# MotorCell.net
KiCad netlist of a schematic drawn in Altium Designer
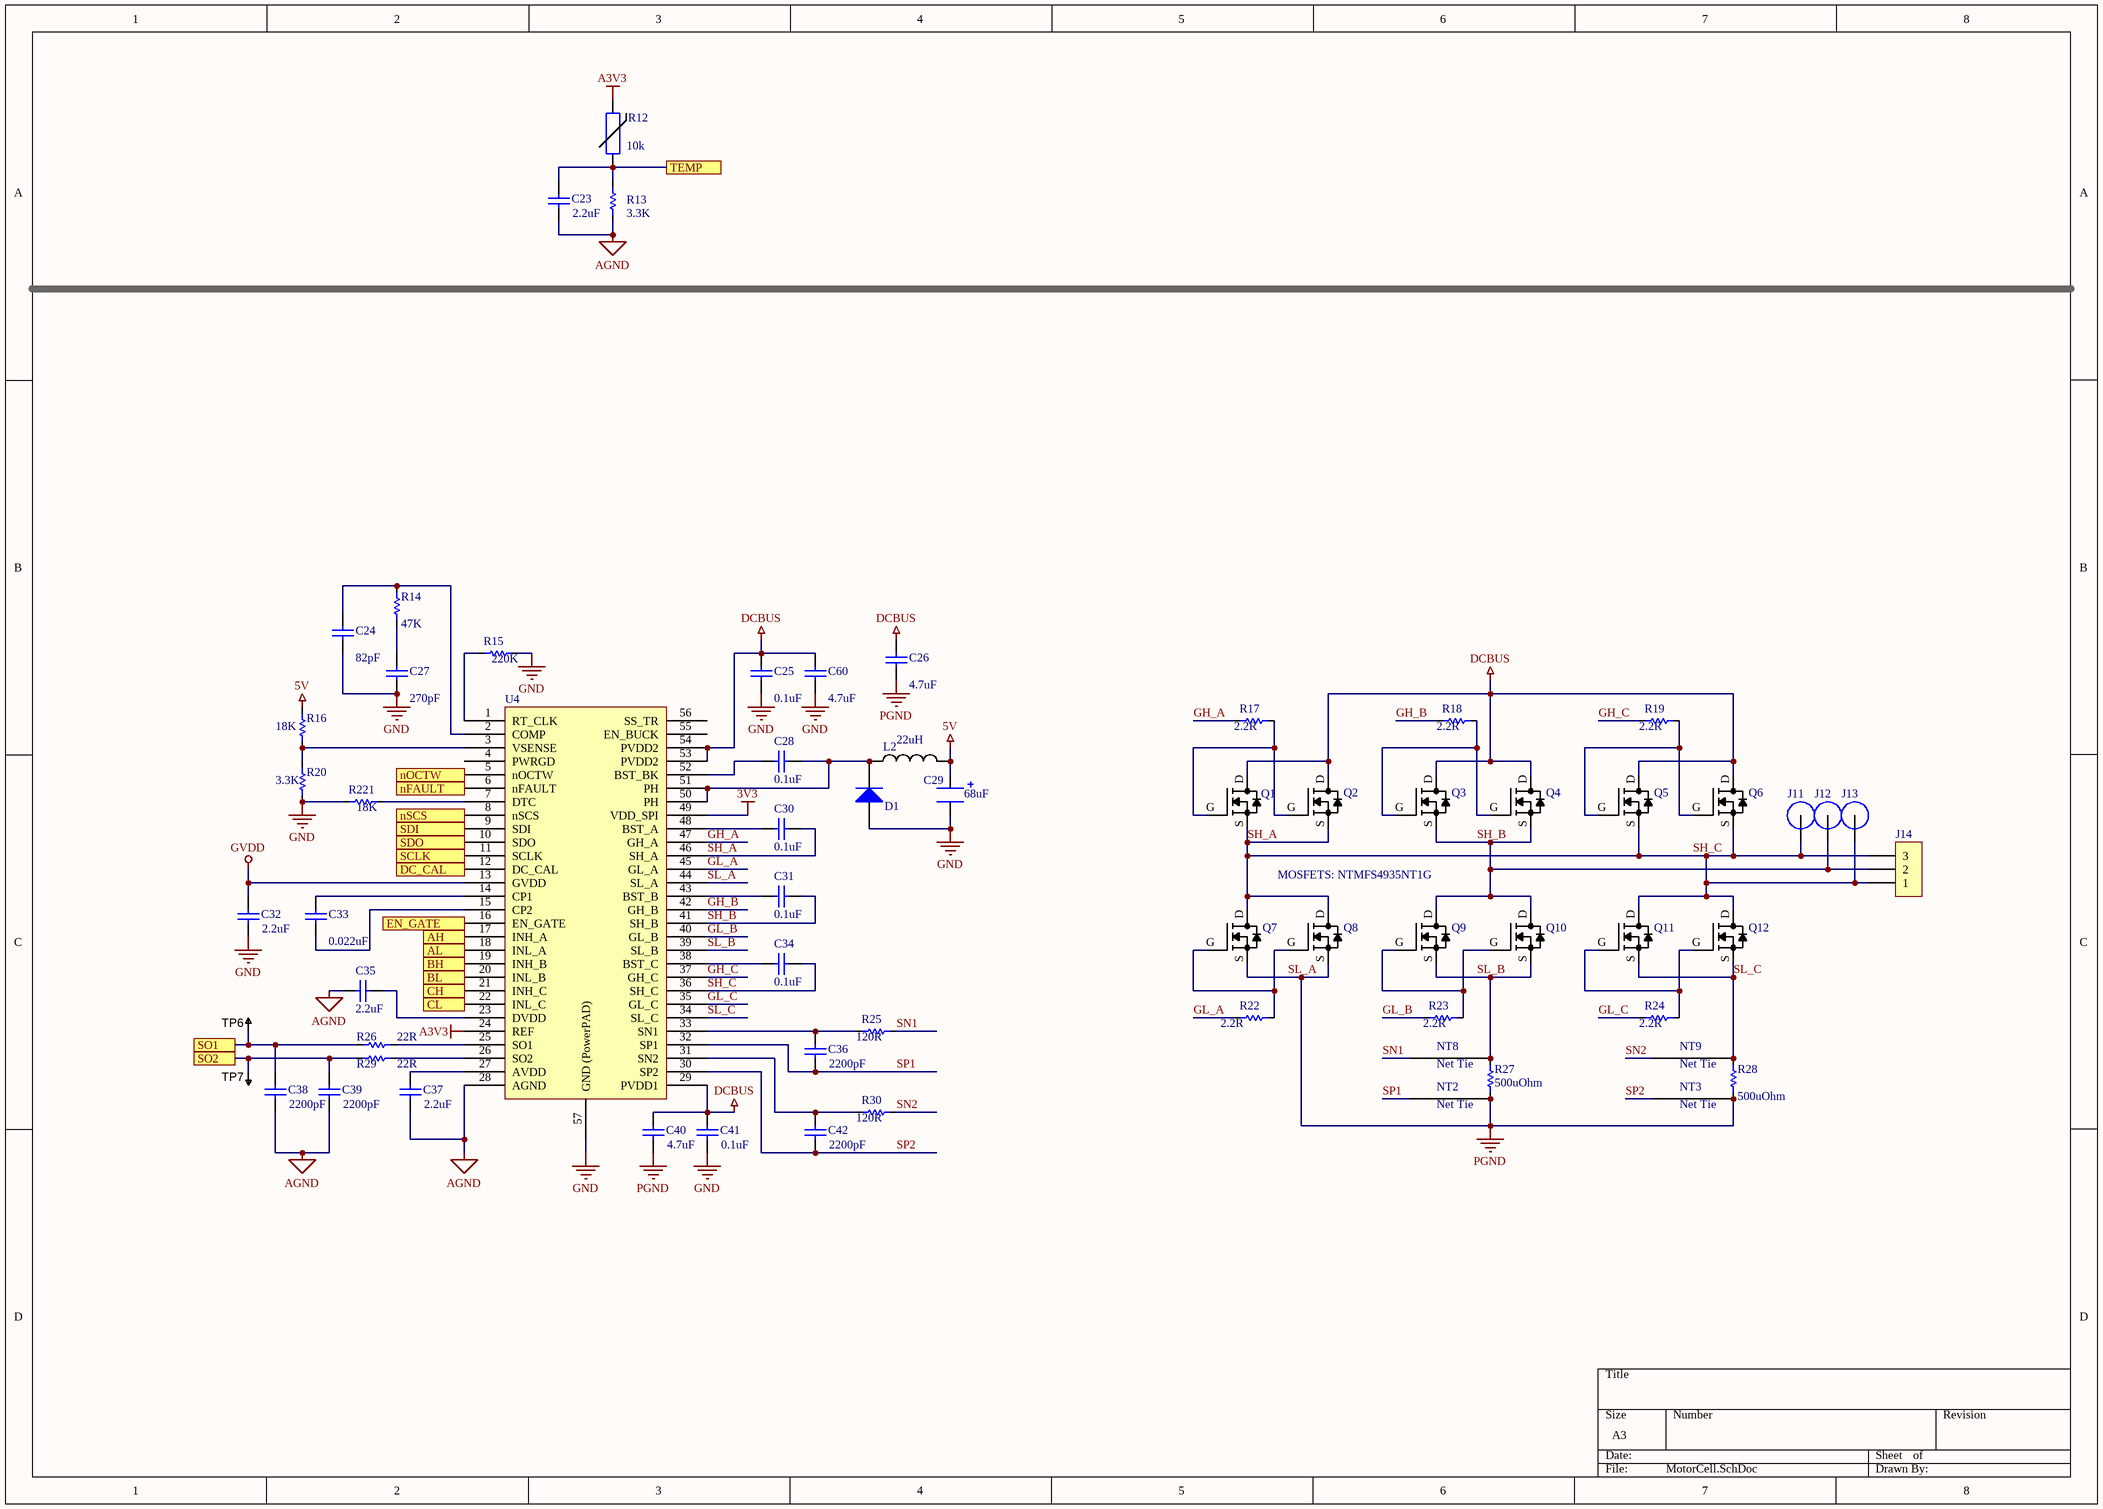
[diagram p0: MotorCell.SchDoc]

(export (version "E")
  (design (tool "Eeschema 10.0.6"))
  (components
    (comp (ref "C23")
      (value "2.2uF")
      (footprint "C0603")
      (description "CAP CER 2.2UF 16V X5R 0603")
      (fields (field (name "Comment") "Cap") (field (name "PUBLISHER") "Altium Limited"))
      (libsource (lib "Component footprints") (part "Cap"))
    )
    (comp (ref "C24")
      (value "82pF")
      (footprint "C0603")
      (description "CAP CER 82PF 100V NP0 0603")
      (fields (field (name "Comment") "Cap") (field (name "PUBLISHER") "Altium Limited"))
      (libsource (lib "Component footprints") (part "Cap"))
    )
    (comp (ref "C25")
      (value "0.1uF")
      (footprint "C0603")
      (description "CAP CER 0.1UF 50V X7R 0603")
      (fields (field (name "Comment") "Cap") (field (name "PUBLISHER") "Altium Limited"))
      (libsource (lib "Component footprints") (part "Cap"))
    )
    (comp (ref "C26")
      (value "4.7uF")
      (footprint "C0805")
      (description "CAP CER 4.7UF 35V X5R 0805")
      (fields (field (name "Comment") "Cap") (field (name "PUBLISHER") "Altium Limited"))
      (libsource (lib "Component footprints") (part "Cap"))
    )
    (comp (ref "C27")
      (value "270pF")
      (footprint "C0603")
      (description "CAP CER 270PF 50V NP0 0603")
      (fields (field (name "Comment") "Cap") (field (name "PUBLISHER") "Altium Limited"))
      (libsource (lib "Component footprints") (part "Cap"))
    )
    (comp (ref "C28")
      (value "0.1uF")
      (footprint "C0603")
      (description "CAP CER 0.1UF 50V X7R 0603")
      (fields (field (name "Comment") "Cap") (field (name "PUBLISHER") "Altium Limited"))
      (libsource (lib "Component footprints") (part "Cap"))
    )
    (comp (ref "C29")
      (value "68uF")
      (footprint "CAPCP6032X28N")
      (description "CAP TANT 68UF 16V 20% 2312 250mOhm")
      (fields (field (name "MANUFACTURER") "KEMET") (field (name "TOLERANCE") "±20%"))
      (libsource (lib "CustomComponents") (part "T495C686M016ATE250"))
    )
    (comp (ref "C30")
      (value "0.1uF")
      (footprint "C0603")
      (description "CAP CER 0.1UF 50V X7R 0603")
      (fields (field (name "Comment") "Cap") (field (name "PUBLISHER") "Altium Limited"))
      (libsource (lib "Component footprints") (part "Cap"))
    )
    (comp (ref "C31")
      (value "0.1uF")
      (footprint "C0603")
      (description "CAP CER 0.1UF 50V X7R 0603")
      (fields (field (name "Comment") "Cap") (field (name "PUBLISHER") "Altium Limited"))
      (libsource (lib "Component footprints") (part "Cap"))
    )
    (comp (ref "C32")
      (value "2.2uF")
      (footprint "C0603")
      (description "CAP CER 2.2UF 16V X5R 0603")
      (fields (field (name "Comment") "Cap") (field (name "PUBLISHER") "Altium Limited"))
      (libsource (lib "Component footprints") (part "Cap"))
    )
    (comp (ref "C33")
      (value "0.022uF")
      (footprint "C0603")
      (description "CAP CER 0.022UF 50V X7R 0603")
      (fields (field (name "Comment") "Cap") (field (name "PUBLISHER") "Altium Limited"))
      (libsource (lib "Component footprints") (part "Cap"))
    )
    (comp (ref "C34")
      (value "0.1uF")
      (footprint "C0603")
      (description "CAP CER 0.1UF 50V X7R 0603")
      (fields (field (name "Comment") "Cap") (field (name "PUBLISHER") "Altium Limited"))
      (libsource (lib "Component footprints") (part "Cap"))
    )
    (comp (ref "C35")
      (value "2.2uF")
      (footprint "C0603")
      (description "CAP CER 2.2UF 16V X5R 0603")
      (fields (field (name "Comment") "Cap") (field (name "PUBLISHER") "Altium Limited"))
      (libsource (lib "Component footprints") (part "Cap"))
    )
    (comp (ref "C36")
      (value "2200pF")
      (footprint "C0603")
      (description "CAP CER 2200PF 50V NP0 0603")
      (fields (field (name "Comment") "Cap") (field (name "PUBLISHER") "Altium Limited"))
      (libsource (lib "Component footprints") (part "Cap"))
    )
    (comp (ref "C37")
      (value "2.2uF")
      (footprint "C0603")
      (description "CAP CER 2.2UF 16V X5R 0603")
      (fields (field (name "Comment") "Cap") (field (name "PUBLISHER") "Altium Limited"))
      (libsource (lib "Component footprints") (part "Cap"))
    )
    (comp (ref "C38")
      (value "2200pF")
      (footprint "C0603")
      (description "CAP CER 2200PF 50V NP0 0603")
      (fields (field (name "Comment") "Cap") (field (name "PUBLISHER") "Altium Limited"))
      (libsource (lib "Component footprints") (part "Cap"))
    )
    (comp (ref "C39")
      (value "2200pF")
      (footprint "C0603")
      (description "CAP CER 2200PF 50V NP0 0603")
      (fields (field (name "Comment") "Cap") (field (name "PUBLISHER") "Altium Limited"))
      (libsource (lib "Component footprints") (part "Cap"))
    )
    (comp (ref "C40")
      (value "4.7uF")
      (footprint "C0805")
      (description "CAP CER 4.7UF 35V X5R 0805")
      (fields (field (name "Comment") "Cap") (field (name "PUBLISHER") "Altium Limited"))
      (libsource (lib "Component footprints") (part "Cap"))
    )
    (comp (ref "C41")
      (value "0.1uF")
      (footprint "C0603")
      (description "CAP CER 0.1UF 50V X7R 0603")
      (fields (field (name "Comment") "Cap") (field (name "PUBLISHER") "Altium Limited"))
      (libsource (lib "Component footprints") (part "Cap"))
    )
    (comp (ref "C42")
      (value "2200pF")
      (footprint "C0603")
      (description "CAP CER 2200PF 50V NP0 0603")
      (fields (field (name "Comment") "Cap") (field (name "PUBLISHER") "Altium Limited"))
      (libsource (lib "Component footprints") (part "Cap"))
    )
    (comp (ref "C60")
      (value "4.7uF")
      (footprint "C0805")
      (description "CAP CER 4.7UF 35V X5R 0805")
      (fields (field (name "Comment") "Cap") (field (name "PUBLISHER") "Altium Limited"))
      (libsource (lib "Component footprints") (part "Cap"))
    )
    (comp (ref "D1")
      (value "~")
      (footprint "DIOM2717X10N")
      (description "Rectifier Diode, Single, 40 V, 1 A, SOD-123FL, 2, 550 mV")
      (libsource (lib "CustomComponents") (part "MBR140SFT1G"))
    )
    (comp (ref "J11")
      (value "~")
      (footprint "M3 Spade Hole")
      (description "M3 Spade Terminal")
      (libsource (lib "CustomComponents") (part "M3 Spade Terminal"))
    )
    (comp (ref "J12")
      (value "~")
      (footprint "M3 Spade Hole")
      (description "M3 Spade Terminal")
      (libsource (lib "CustomComponents") (part "M3 Spade Terminal"))
    )
    (comp (ref "J13")
      (value "~")
      (footprint "M3 Spade Hole")
      (description "M3 Spade Terminal")
      (libsource (lib "CustomComponents") (part "M3 Spade Terminal"))
    )
    (comp (ref "J14")
      (value "1704936")
      (footprint "1704936")
      (description "CONN TERM BLOCK 3POS 7.62MM")
      (fields (field (name "MANUFACTURER") "Phoenix Contact") (field (name "VOLTAGE") "300V"))
      (libsource (lib "CustomComponents") (part "1704936"))
    )
    (comp (ref "L2")
      (value "22uH")
      (footprint "INDC6060X28N")
      (description "INDUCTOR 22UH 1.4A 175.5 MOHM")
      (libsource (lib "CustomComponents") (part "NR6028T220M"))
    )
    (comp (ref "NT2")
      (value "0.25mm")
      (footprint "NetTie_0.25mm")
      (libsource (lib "CustomComponents") (part "NetTie_0.25mm"))
    )
    (comp (ref "NT3")
      (value "0.25mm")
      (footprint "NetTie_0.25mm")
      (libsource (lib "CustomComponents") (part "NetTie_0.25mm"))
    )
    (comp (ref "NT8")
      (value "0.25mm")
      (footprint "NetTie_0.25mm")
      (libsource (lib "CustomComponents") (part "NetTie_0.25mm"))
    )
    (comp (ref "NT9")
      (value "0.25mm")
      (footprint "NetTie_0.25mm")
      (libsource (lib "CustomComponents") (part "NetTie_0.25mm"))
    )
    (comp (ref "Q1")
      (value "~")
      (footprint "SO8FL")
      (description "MOSFET N-CH 30V 13A SO8FL")
      (fields
        (field (name "MANUFACTURER") "ON Semiconductor")
        (field (name "MANUFACTURER PART NUMBER") "NTMFS4935NT1G")
      )
      (libsource (lib "CustomComponents") (part "NTMFS4935NT1G"))
    )
    (comp (ref "Q2")
      (value "FILL_FOOTPRINT")
      (footprint "SO8FL_FILL")
      (description "MOSFET N-CH 30V 13A SO8FL")
      (fields
        (field (name "MANUFACTURER") "ON Semiconductor")
        (field (name "MANUFACTURER PART NUMBER") "NTMFS4935NT1G")
      )
      (libsource (lib "CustomComponents") (part "NTMFS4935NT1G"))
    )
    (comp (ref "Q3")
      (value "~")
      (footprint "SO8FL")
      (description "MOSFET N-CH 30V 13A SO8FL")
      (fields
        (field (name "MANUFACTURER") "ON Semiconductor")
        (field (name "MANUFACTURER PART NUMBER") "NTMFS4935NT1G")
      )
      (libsource (lib "CustomComponents") (part "NTMFS4935NT1G"))
    )
    (comp (ref "Q4")
      (value "FILL_FOOTPRINT")
      (footprint "SO8FL_FILL")
      (description "MOSFET N-CH 30V 13A SO8FL")
      (fields
        (field (name "MANUFACTURER") "ON Semiconductor")
        (field (name "MANUFACTURER PART NUMBER") "NTMFS4935NT1G")
      )
      (libsource (lib "CustomComponents") (part "NTMFS4935NT1G"))
    )
    (comp (ref "Q5")
      (value "~")
      (footprint "SO8FL")
      (description "MOSFET N-CH 30V 13A SO8FL")
      (fields
        (field (name "MANUFACTURER") "ON Semiconductor")
        (field (name "MANUFACTURER PART NUMBER") "NTMFS4935NT1G")
      )
      (libsource (lib "CustomComponents") (part "NTMFS4935NT1G"))
    )
    (comp (ref "Q6")
      (value "FILL_FOOTPRINT")
      (footprint "SO8FL_FILL")
      (description "MOSFET N-CH 30V 13A SO8FL")
      (fields
        (field (name "MANUFACTURER") "ON Semiconductor")
        (field (name "MANUFACTURER PART NUMBER") "NTMFS4935NT1G")
      )
      (libsource (lib "CustomComponents") (part "NTMFS4935NT1G"))
    )
    (comp (ref "Q7")
      (value "~")
      (footprint "SO8FL")
      (description "MOSFET N-CH 30V 13A SO8FL")
      (fields
        (field (name "MANUFACTURER") "ON Semiconductor")
        (field (name "MANUFACTURER PART NUMBER") "NTMFS4935NT1G")
      )
      (libsource (lib "CustomComponents") (part "NTMFS4935NT1G"))
    )
    (comp (ref "Q8")
      (value "~")
      (footprint "SO8FL")
      (description "MOSFET N-CH 30V 13A SO8FL")
      (fields
        (field (name "MANUFACTURER") "ON Semiconductor")
        (field (name "MANUFACTURER PART NUMBER") "NTMFS4935NT1G")
      )
      (libsource (lib "CustomComponents") (part "NTMFS4935NT1G"))
    )
    (comp (ref "Q9")
      (value "~")
      (footprint "SO8FL")
      (description "MOSFET N-CH 30V 13A SO8FL")
      (fields
        (field (name "MANUFACTURER") "ON Semiconductor")
        (field (name "MANUFACTURER PART NUMBER") "NTMFS4935NT1G")
      )
      (libsource (lib "CustomComponents") (part "NTMFS4935NT1G"))
    )
    (comp (ref "Q10")
      (value "~")
      (footprint "SO8FL")
      (description "MOSFET N-CH 30V 13A SO8FL")
      (fields
        (field (name "MANUFACTURER") "ON Semiconductor")
        (field (name "MANUFACTURER PART NUMBER") "NTMFS4935NT1G")
      )
      (libsource (lib "CustomComponents") (part "NTMFS4935NT1G"))
    )
    (comp (ref "Q11")
      (value "~")
      (footprint "SO8FL")
      (description "MOSFET N-CH 30V 13A SO8FL")
      (fields
        (field (name "MANUFACTURER") "ON Semiconductor")
        (field (name "MANUFACTURER PART NUMBER") "NTMFS4935NT1G")
      )
      (libsource (lib "CustomComponents") (part "NTMFS4935NT1G"))
    )
    (comp (ref "Q12")
      (value "~")
      (footprint "SO8FL")
      (description "MOSFET N-CH 30V 13A SO8FL")
      (fields
        (field (name "MANUFACTURER") "ON Semiconductor")
        (field (name "MANUFACTURER PART NUMBER") "NTMFS4935NT1G")
      )
      (libsource (lib "CustomComponents") (part "NTMFS4935NT1G"))
    )
    (comp (ref "R12")
      (value "10k")
      (footprint "RESC1005X40N")
      (description "THERMISTOR 10K OHM NTC 0402 SMD")
      (libsource (lib "CustomComponents") (part "NCP15XH103F03RC"))
    )
    (comp (ref "R13")
      (value "3.3K")
      (footprint "R0603")
      (description "Resistor")
      (fields (field (name "Comment") "Res") (field (name "PUBLISHER") "Altium Limited"))
      (libsource (lib "Component footprints") (part "Res"))
    )
    (comp (ref "R14")
      (value "47K")
      (footprint "R0603")
      (description "Resistor")
      (fields (field (name "Comment") "Res") (field (name "PUBLISHER") "Altium Limited"))
      (libsource (lib "Component footprints") (part "Res"))
    )
    (comp (ref "R15")
      (value "220K")
      (footprint "R0603")
      (description "Resistor")
      (fields (field (name "Comment") "Res") (field (name "PUBLISHER") "Altium Limited"))
      (libsource (lib "Component footprints") (part "Res"))
    )
    (comp (ref "R16")
      (value "18K")
      (footprint "R0603")
      (description "Resistor")
      (fields (field (name "Comment") "Res") (field (name "PUBLISHER") "Altium Limited"))
      (libsource (lib "Component footprints") (part "Res"))
    )
    (comp (ref "R17")
      (value "2.2R")
      (footprint "R0603")
      (description "Resistor")
      (fields (field (name "Comment") "Res") (field (name "PUBLISHER") "Altium Limited"))
      (libsource (lib "Component footprints") (part "Res"))
    )
    (comp (ref "R18")
      (value "2.2R")
      (footprint "R0603")
      (description "Resistor")
      (fields (field (name "Comment") "Res") (field (name "PUBLISHER") "Altium Limited"))
      (libsource (lib "Component footprints") (part "Res"))
    )
    (comp (ref "R19")
      (value "2.2R")
      (footprint "R0603")
      (description "Resistor")
      (fields (field (name "Comment") "Res") (field (name "PUBLISHER") "Altium Limited"))
      (libsource (lib "Component footprints") (part "Res"))
    )
    (comp (ref "R20")
      (value "3.3K")
      (footprint "R0603")
      (description "Resistor")
      (fields (field (name "Comment") "Res") (field (name "PUBLISHER") "Altium Limited"))
      (libsource (lib "Component footprints") (part "Res"))
    )
    (comp (ref "R22")
      (value "2.2R")
      (footprint "R0603")
      (description "Resistor")
      (fields (field (name "Comment") "Res") (field (name "PUBLISHER") "Altium Limited"))
      (libsource (lib "Component footprints") (part "Res"))
    )
    (comp (ref "R23")
      (value "2.2R")
      (footprint "R0603")
      (description "Resistor")
      (fields (field (name "Comment") "Res") (field (name "PUBLISHER") "Altium Limited"))
      (libsource (lib "Component footprints") (part "Res"))
    )
    (comp (ref "R24")
      (value "2.2R")
      (footprint "R0603")
      (description "Resistor")
      (fields (field (name "Comment") "Res") (field (name "PUBLISHER") "Altium Limited"))
      (libsource (lib "Component footprints") (part "Res"))
    )
    (comp (ref "R25")
      (value "120R")
      (footprint "R0603")
      (description "Resistor")
      (fields (field (name "Comment") "Res") (field (name "PUBLISHER") "Altium Limited"))
      (libsource (lib "Component footprints") (part "Res"))
    )
    (comp (ref "R26")
      (value "22R")
      (footprint "R0603")
      (description "Resistor")
      (fields (field (name "Comment") "Res") (field (name "PUBLISHER") "Altium Limited"))
      (libsource (lib "Component footprints") (part "Res"))
    )
    (comp (ref "R27")
      (value "500uOhm")
      (footprint "R2512")
      (description "RES SMD 0.0005 OHM 1% 3W 2512")
      (fields (field (name "Comment") "Res") (field (name "PUBLISHER") "Altium Limited"))
      (libsource (lib "Component footprints") (part "Res"))
    )
    (comp (ref "R28")
      (value "500uOhm")
      (footprint "R2512")
      (description "RES SMD 0.0005 OHM 1% 3W 2512")
      (fields (field (name "Comment") "Res") (field (name "PUBLISHER") "Altium Limited"))
      (libsource (lib "Component footprints") (part "Res"))
    )
    (comp (ref "R29")
      (value "22R")
      (footprint "R0603")
      (description "Resistor")
      (fields (field (name "Comment") "Res") (field (name "PUBLISHER") "Altium Limited"))
      (libsource (lib "Component footprints") (part "Res"))
    )
    (comp (ref "R30")
      (value "120R")
      (footprint "R0603")
      (description "Resistor")
      (fields (field (name "Comment") "Res") (field (name "PUBLISHER") "Altium Limited"))
      (libsource (lib "Component footprints") (part "Res"))
    )
    (comp (ref "R221")
      (value "18K")
      (footprint "R0603")
      (description "Resistor")
      (fields (field (name "Comment") "Res") (field (name "PUBLISHER") "Altium Limited"))
      (libsource (lib "Component footprints") (part "Res"))
    )
    (comp (ref "TP6")
      (value "TESTPOINT")
      (footprint "TP-R30")
      (description "SMD test pin")
      (libsource (lib "PBL - Test Points") (part "TESTPOINT"))
    )
    (comp (ref "TP7")
      (value "TESTPOINT")
      (footprint "TP-R30")
      (description "SMD test pin")
      (libsource (lib "PBL - Test Points") (part "TESTPOINT"))
    )
    (comp (ref "U4")
      (value "~")
      (footprint "TSSOP50P810X120_HS-57N")
      (description "MOTOR DRIVER, 3PH, 56HTSSOP")
      (libsource (lib "CustomComponents") (part "DRV8301"))
    )
  )
  (nets
    (net (code "1") (name "/AH") (class "Default")
      (node (ref "U4") (pin "17") (pinfunction "INH_A_17") (pintype "passive"))
    )
    (net (code "2") (name "/AL") (class "Default")
      (node (ref "U4") (pin "18") (pinfunction "INL_A_18") (pintype "passive"))
    )
    (net (code "3") (name "/BH") (class "Default")
      (node (ref "U4") (pin "19") (pinfunction "INH_B_19") (pintype "passive"))
    )
    (net (code "4") (name "/BL") (class "Default")
      (node (ref "U4") (pin "20") (pinfunction "INL_B_20") (pintype "passive"))
    )
    (net (code "5") (name "/CH") (class "Default")
      (node (ref "U4") (pin "21") (pinfunction "INH_C_21") (pintype "passive"))
    )
    (net (code "6") (name "/CL") (class "Default")
      (node (ref "U4") (pin "22") (pinfunction "INL_C_22") (pintype "passive"))
    )
    (net (code "7") (name "/DC_CAL") (class "Default")
      (node (ref "U4") (pin "12") (pinfunction "DC_CAL_12") (pintype "passive"))
    )
    (net (code "8") (name "/EN_GATE") (class "Default")
      (node (ref "U4") (pin "16") (pinfunction "EN_GATE_16") (pintype "passive"))
    )
    (net (code "9") (name "/GH_A") (class "Default")
      (node (ref "R17") (pin "2") (pinfunction "2_2") (pintype "passive"))
      (node (ref "U4") (pin "47") (pinfunction "GH_A_47") (pintype "passive"))
    )
    (net (code "10") (name "/GH_B") (class "Default")
      (node (ref "R18") (pin "2") (pinfunction "2_2") (pintype "passive"))
      (node (ref "U4") (pin "42") (pinfunction "GH_B_42") (pintype "passive"))
    )
    (net (code "11") (name "/GH_C") (class "Default")
      (node (ref "R19") (pin "2") (pinfunction "2_2") (pintype "passive"))
      (node (ref "U4") (pin "37") (pinfunction "GH_C_37") (pintype "passive"))
    )
    (net (code "12") (name "/GL_A") (class "Default")
      (node (ref "R22") (pin "2") (pinfunction "2_2") (pintype "passive"))
      (node (ref "U4") (pin "45") (pinfunction "GL_A_45") (pintype "passive"))
    )
    (net (code "13") (name "/GL_B") (class "Default")
      (node (ref "R23") (pin "2") (pinfunction "2_2") (pintype "passive"))
      (node (ref "U4") (pin "40") (pinfunction "GL_B_40") (pintype "passive"))
    )
    (net (code "14") (name "/GL_C") (class "Default")
      (node (ref "R24") (pin "2") (pinfunction "2_2") (pintype "passive"))
      (node (ref "U4") (pin "35") (pinfunction "GL_C_35") (pintype "passive"))
    )
    (net (code "15") (name "/SCLK") (class "Default")
      (node (ref "U4") (pin "11") (pinfunction "SCLK_11") (pintype "passive"))
    )
    (net (code "16") (name "/SDI") (class "Default")
      (node (ref "U4") (pin "9") (pinfunction "SDI_9") (pintype "passive"))
    )
    (net (code "17") (name "/SDO") (class "Default")
      (node (ref "U4") (pin "10") (pinfunction "SDO_10") (pintype "passive"))
    )
    (net (code "18") (name "/SH_A") (class "Default")
      (node (ref "C30") (pin "1") (pinfunction "1_1") (pintype "passive"))
      (node (ref "C34") (pin "1") (pinfunction "1_1") (pintype "passive"))
      (node (ref "J11") (pin "1") (pinfunction "1_1") (pintype "passive"))
      (node (ref "J13") (pin "1") (pinfunction "1_1") (pintype "passive"))
      (node (ref "J14") (pin "1") (pinfunction "1_1") (pintype "passive"))
      (node (ref "J14") (pin "3") (pinfunction "3_3") (pintype "passive"))
      (node (ref "Q1") (pin "S") (pinfunction "S_S") (pintype "passive"))
      (node (ref "Q11") (pin "D") (pinfunction "D_D") (pintype "passive"))
      (node (ref "Q12") (pin "D") (pinfunction "D_D") (pintype "passive"))
      (node (ref "Q2") (pin "S") (pinfunction "S_S") (pintype "passive"))
      (node (ref "Q5") (pin "S") (pinfunction "S_S") (pintype "passive"))
      (node (ref "Q6") (pin "S") (pinfunction "S_S") (pintype "passive"))
      (node (ref "Q7") (pin "D") (pinfunction "D_D") (pintype "passive"))
      (node (ref "Q8") (pin "D") (pinfunction "D_D") (pintype "passive"))
      (node (ref "U4") (pin "36") (pinfunction "SH_C_36") (pintype "passive"))
      (node (ref "U4") (pin "46") (pinfunction "SH_A_46") (pintype "passive"))
    )
    (net (code "19") (name "/SH_B") (class "Default")
      (node (ref "C31") (pin "1") (pinfunction "1_1") (pintype "passive"))
      (node (ref "J12") (pin "1") (pinfunction "1_1") (pintype "passive"))
      (node (ref "J14") (pin "2") (pinfunction "2_2") (pintype "passive"))
      (node (ref "Q10") (pin "D") (pinfunction "D_D") (pintype "passive"))
      (node (ref "Q3") (pin "S") (pinfunction "S_S") (pintype "passive"))
      (node (ref "Q4") (pin "S") (pinfunction "S_S") (pintype "passive"))
      (node (ref "Q9") (pin "D") (pinfunction "D_D") (pintype "passive"))
      (node (ref "U4") (pin "41") (pinfunction "SH_B_41") (pintype "passive"))
    )
    (net (code "20") (name "/SL_B") (class "Default")
      (node (ref "NT8") (pin "2") (pintype "passive"))
      (node (ref "Q10") (pin "S") (pinfunction "S_S") (pintype "passive"))
      (node (ref "Q9") (pin "S") (pinfunction "S_S") (pintype "passive"))
      (node (ref "R27") (pin "1") (pinfunction "1_1") (pintype "passive"))
      (node (ref "U4") (pin "39") (pinfunction "SL_B_39") (pintype "passive"))
    )
    (net (code "21") (name "/SL_C") (class "Default")
      (node (ref "NT9") (pin "2") (pintype "passive"))
      (node (ref "Q11") (pin "S") (pinfunction "S_S") (pintype "passive"))
      (node (ref "Q12") (pin "S") (pinfunction "S_S") (pintype "passive"))
      (node (ref "R28") (pin "2") (pinfunction "2_2") (pintype "passive"))
      (node (ref "U4") (pin "34") (pinfunction "SL_C_34") (pintype "passive"))
    )
    (net (code "22") (name "/SN1") (class "Default")
      (node (ref "NT8") (pin "1") (pintype "passive"))
      (node (ref "R25") (pin "2") (pinfunction "2_2") (pintype "passive"))
    )
    (net (code "23") (name "/SN2") (class "Default")
      (node (ref "NT9") (pin "1") (pintype "passive"))
      (node (ref "R30") (pin "2") (pinfunction "2_2") (pintype "passive"))
    )
    (net (code "24") (name "/SO1") (class "Default")
      (node (ref "C38") (pin "2") (pinfunction "2_2") (pintype "passive"))
      (node (ref "R26") (pin "1") (pinfunction "1_1") (pintype "passive"))
      (node (ref "TP6") (pin "1") (pintype "passive"))
    )
    (net (code "25") (name "/SO2") (class "Default")
      (node (ref "C39") (pin "2") (pinfunction "2_2") (pintype "passive"))
      (node (ref "R29") (pin "1") (pinfunction "1_1") (pintype "passive"))
      (node (ref "TP7") (pin "1") (pintype "passive"))
    )
    (net (code "26") (name "/SP1") (class "Default")
      (node (ref "C36") (pin "1") (pinfunction "1_1") (pintype "passive"))
      (node (ref "NT2") (pin "1") (pintype "passive"))
      (node (ref "U4") (pin "32") (pinfunction "SP1_32") (pintype "passive"))
    )
    (net (code "27") (name "/SP2") (class "Default")
      (node (ref "C42") (pin "1") (pinfunction "1_1") (pintype "passive"))
      (node (ref "NT3") (pin "1") (pintype "passive"))
      (node (ref "U4") (pin "30") (pinfunction "SP2_30") (pintype "passive"))
    )
    (net (code "28") (name "/TEMP") (class "Default")
      (node (ref "C23") (pin "2") (pinfunction "2_2") (pintype "passive"))
      (node (ref "R12") (pin "1") (pinfunction "0_1") (pintype "passive"))
      (node (ref "R13") (pin "2") (pinfunction "2_2") (pintype "passive"))
    )
    (net (code "29") (name "/nFAULT") (class "Default")
      (node (ref "U4") (pin "6") (pinfunction "nFAULT_6") (pintype "passive"))
    )
    (net (code "30") (name "/nOCTW") (class "Default")
      (node (ref "U4") (pin "5") (pinfunction "nOCTW_5") (pintype "passive"))
    )
    (net (code "31") (name "/nSCS") (class "Default")
      (node (ref "U4") (pin "8") (pinfunction "nSCS_8") (pintype "passive"))
    )
    (net (code "32") (name "3V3") (class "Default")
      (node (ref "U4") (pin "49") (pinfunction "VDD_SPI_49") (pintype "passive"))
    )
    (net (code "33") (name "5V") (class "Default")
      (node (ref "C29") (pin "1") (pinfunction "1_1") (pintype "passive"))
      (node (ref "L2") (pin "2") (pinfunction "2_2") (pintype "passive"))
      (node (ref "R16") (pin "1") (pinfunction "1_1") (pintype "passive"))
    )
    (net (code "34") (name "A3V3") (class "Default")
      (node (ref "R12") (pin "2") (pinfunction "0_2") (pintype "passive"))
      (node (ref "U4") (pin "24") (pinfunction "REF_24") (pintype "passive"))
    )
    (net (code "35") (name "AGND") (class "Default")
      (node (ref "C23") (pin "1") (pinfunction "1_1") (pintype "passive"))
      (node (ref "C35") (pin "2") (pinfunction "2_2") (pintype "passive"))
      (node (ref "C37") (pin "1") (pinfunction "1_1") (pintype "passive"))
      (node (ref "C38") (pin "1") (pinfunction "1_1") (pintype "passive"))
      (node (ref "C39") (pin "1") (pinfunction "1_1") (pintype "passive"))
      (node (ref "R13") (pin "1") (pinfunction "1_1") (pintype "passive"))
      (node (ref "U4") (pin "28") (pinfunction "AGND_28") (pintype "passive"))
    )
    (net (code "36") (name "DCBUS") (class "Default")
      (node (ref "C25") (pin "2") (pinfunction "2_2") (pintype "passive"))
      (node (ref "C26") (pin "2") (pinfunction "2_2") (pintype "passive"))
      (node (ref "C40") (pin "2") (pinfunction "2_2") (pintype "passive"))
      (node (ref "C41") (pin "2") (pinfunction "2_2") (pintype "passive"))
      (node (ref "C60") (pin "2") (pinfunction "2_2") (pintype "passive"))
      (node (ref "Q1") (pin "D") (pinfunction "D_D") (pintype "passive"))
      (node (ref "Q2") (pin "D") (pinfunction "D_D") (pintype "passive"))
      (node (ref "Q3") (pin "D") (pinfunction "D_D") (pintype "passive"))
      (node (ref "Q4") (pin "D") (pinfunction "D_D") (pintype "passive"))
      (node (ref "Q5") (pin "D") (pinfunction "D_D") (pintype "passive"))
      (node (ref "Q6") (pin "D") (pinfunction "D_D") (pintype "passive"))
      (node (ref "U4") (pin "29") (pinfunction "PVDD1_29") (pintype "passive"))
      (node (ref "U4") (pin "53") (pinfunction "PVDD2_53") (pintype "passive"))
      (node (ref "U4") (pin "54") (pinfunction "PVDD2_54") (pintype "passive"))
    )
    (net (code "37") (name "GND") (class "Default")
      (node (ref "C24") (pin "1") (pinfunction "1_1") (pintype "passive"))
      (node (ref "C25") (pin "1") (pinfunction "1_1") (pintype "passive"))
      (node (ref "C27") (pin "1") (pinfunction "1_1") (pintype "passive"))
      (node (ref "C29") (pin "2") (pinfunction "2_2") (pintype "passive"))
      (node (ref "C32") (pin "1") (pinfunction "1_1") (pintype "passive"))
      (node (ref "C41") (pin "1") (pinfunction "1_1") (pintype "passive"))
      (node (ref "C60") (pin "1") (pinfunction "1_1") (pintype "passive"))
      (node (ref "D1") (pin "A") (pinfunction "A_A") (pintype "passive"))
      (node (ref "R15") (pin "1") (pinfunction "1_1") (pintype "passive"))
      (node (ref "R20") (pin "2") (pinfunction "2_2") (pintype "passive"))
      (node (ref "R221") (pin "1") (pinfunction "1_1") (pintype "passive"))
      (node (ref "U4") (pin "57") (pinfunction "GND_(PowerPAD)_57") (pintype "passive"))
    )
    (net (code "38") (name "GVDD") (class "Default")
      (node (ref "C32") (pin "2") (pinfunction "2_2") (pintype "passive"))
      (node (ref "U4") (pin "13") (pinfunction "GVDD_13") (pintype "passive"))
    )
    (net (code "39") (name "Net-(C27-Pad2)") (class "Default")
      (node (ref "C27") (pin "2") (pinfunction "2_2") (pintype "passive"))
      (node (ref "R14") (pin "2") (pinfunction "2_2") (pintype "passive"))
    )
    (net (code "40") (name "Net-(C28-Pad1)") (class "Default")
      (node (ref "C28") (pin "1") (pinfunction "1_1") (pintype "passive"))
      (node (ref "D1") (pin "K") (pinfunction "K_K") (pintype "passive"))
      (node (ref "L2") (pin "1") (pinfunction "1_1") (pintype "passive"))
      (node (ref "U4") (pin "50") (pinfunction "PH_50") (pintype "passive"))
      (node (ref "U4") (pin "51") (pinfunction "PH_51") (pintype "passive"))
    )
    (net (code "41") (name "Net-(Q1-PadG)") (class "Default")
      (node (ref "Q1") (pin "G") (pinfunction "G_G") (pintype "passive"))
      (node (ref "Q2") (pin "G") (pinfunction "G_G") (pintype "passive"))
      (node (ref "R17") (pin "1") (pinfunction "1_1") (pintype "passive"))
    )
    (net (code "42") (name "Net-(Q3-PadG)") (class "Default")
      (node (ref "Q3") (pin "G") (pinfunction "G_G") (pintype "passive"))
      (node (ref "Q4") (pin "G") (pinfunction "G_G") (pintype "passive"))
      (node (ref "R18") (pin "1") (pinfunction "1_1") (pintype "passive"))
    )
    (net (code "43") (name "Net-(Q5-PadG)") (class "Default")
      (node (ref "Q5") (pin "G") (pinfunction "G_G") (pintype "passive"))
      (node (ref "Q6") (pin "G") (pinfunction "G_G") (pintype "passive"))
      (node (ref "R19") (pin "1") (pinfunction "1_1") (pintype "passive"))
    )
    (net (code "44") (name "Net-(Q7-PadG)") (class "Default")
      (node (ref "Q7") (pin "G") (pinfunction "G_G") (pintype "passive"))
      (node (ref "Q8") (pin "G") (pinfunction "G_G") (pintype "passive"))
      (node (ref "R22") (pin "1") (pinfunction "1_1") (pintype "passive"))
    )
    (net (code "45") (name "Net-(Q10-PadG)") (class "Default")
      (node (ref "Q10") (pin "G") (pinfunction "G_G") (pintype "passive"))
      (node (ref "Q9") (pin "G") (pinfunction "G_G") (pintype "passive"))
      (node (ref "R23") (pin "1") (pinfunction "1_1") (pintype "passive"))
    )
    (net (code "46") (name "Net-(Q11-PadG)") (class "Default")
      (node (ref "Q11") (pin "G") (pinfunction "G_G") (pintype "passive"))
      (node (ref "Q12") (pin "G") (pinfunction "G_G") (pintype "passive"))
      (node (ref "R24") (pin "1") (pinfunction "1_1") (pintype "passive"))
    )
    (net (code "47") (name "Net-(U4-AVDD)") (class "Default")
      (node (ref "C37") (pin "2") (pinfunction "2_2") (pintype "passive"))
      (node (ref "U4") (pin "27") (pinfunction "AVDD_27") (pintype "passive"))
    )
    (net (code "48") (name "Net-(U4-BST_A)") (class "Default")
      (node (ref "C30") (pin "2") (pinfunction "2_2") (pintype "passive"))
      (node (ref "U4") (pin "48") (pinfunction "BST_A_48") (pintype "passive"))
    )
    (net (code "49") (name "Net-(U4-BST_B)") (class "Default")
      (node (ref "C31") (pin "2") (pinfunction "2_2") (pintype "passive"))
      (node (ref "U4") (pin "43") (pinfunction "BST_B_43") (pintype "passive"))
    )
    (net (code "50") (name "Net-(U4-BST_BK)") (class "Default")
      (node (ref "C28") (pin "2") (pinfunction "2_2") (pintype "passive"))
      (node (ref "U4") (pin "52") (pinfunction "BST_BK_52") (pintype "passive"))
    )
    (net (code "51") (name "Net-(U4-BST_C)") (class "Default")
      (node (ref "C34") (pin "2") (pinfunction "2_2") (pintype "passive"))
      (node (ref "U4") (pin "38") (pinfunction "BST_C_38") (pintype "passive"))
    )
    (net (code "52") (name "Net-(U4-COMP)") (class "Default")
      (node (ref "C24") (pin "2") (pinfunction "2_2") (pintype "passive"))
      (node (ref "R14") (pin "1") (pinfunction "1_1") (pintype "passive"))
      (node (ref "U4") (pin "2") (pinfunction "COMP_2") (pintype "passive"))
    )
    (net (code "53") (name "Net-(U4-CP1)") (class "Default")
      (node (ref "C33") (pin "2") (pinfunction "2_2") (pintype "passive"))
      (node (ref "U4") (pin "14") (pinfunction "CP1_14") (pintype "passive"))
    )
    (net (code "54") (name "Net-(U4-CP2)") (class "Default")
      (node (ref "C33") (pin "1") (pinfunction "1_1") (pintype "passive"))
      (node (ref "U4") (pin "15") (pinfunction "CP2_15") (pintype "passive"))
    )
    (net (code "55") (name "Net-(U4-DTC)") (class "Default")
      (node (ref "R221") (pin "2") (pinfunction "2_2") (pintype "passive"))
      (node (ref "U4") (pin "7") (pinfunction "DTC_7") (pintype "passive"))
    )
    (net (code "56") (name "Net-(U4-DVDD)") (class "Default")
      (node (ref "C35") (pin "1") (pinfunction "1_1") (pintype "passive"))
      (node (ref "U4") (pin "23") (pinfunction "DVDD_23") (pintype "passive"))
    )
    (net (code "57") (name "Net-(U4-RT_CLK)") (class "Default")
      (node (ref "R15") (pin "2") (pinfunction "2_2") (pintype "passive"))
      (node (ref "U4") (pin "1") (pinfunction "RT_CLK_1") (pintype "passive"))
    )
    (net (code "58") (name "Net-(U4-SN1)") (class "Default")
      (node (ref "C36") (pin "2") (pinfunction "2_2") (pintype "passive"))
      (node (ref "R25") (pin "1") (pinfunction "1_1") (pintype "passive"))
      (node (ref "U4") (pin "33") (pinfunction "SN1_33") (pintype "passive"))
    )
    (net (code "59") (name "Net-(U4-SN2)") (class "Default")
      (node (ref "C42") (pin "2") (pinfunction "2_2") (pintype "passive"))
      (node (ref "R30") (pin "1") (pinfunction "1_1") (pintype "passive"))
      (node (ref "U4") (pin "31") (pinfunction "SN2_31") (pintype "passive"))
    )
    (net (code "60") (name "Net-(U4-SO1)") (class "Default")
      (node (ref "R26") (pin "2") (pinfunction "2_2") (pintype "passive"))
      (node (ref "U4") (pin "25") (pinfunction "SO1_25") (pintype "passive"))
    )
    (net (code "61") (name "Net-(U4-SO2)") (class "Default")
      (node (ref "R29") (pin "2") (pinfunction "2_2") (pintype "passive"))
      (node (ref "U4") (pin "26") (pinfunction "SO2_26") (pintype "passive"))
    )
    (net (code "62") (name "Net-(U4-VSENSE)") (class "Default")
      (node (ref "R16") (pin "2") (pinfunction "2_2") (pintype "passive"))
      (node (ref "R20") (pin "1") (pinfunction "1_1") (pintype "passive"))
      (node (ref "U4") (pin "3") (pinfunction "VSENSE_3") (pintype "passive"))
    )
    (net (code "63") (name "PGND") (class "Default")
      (node (ref "C26") (pin "1") (pinfunction "1_1") (pintype "passive"))
      (node (ref "C40") (pin "1") (pinfunction "1_1") (pintype "passive"))
      (node (ref "NT2") (pin "2") (pintype "passive"))
      (node (ref "NT3") (pin "2") (pintype "passive"))
      (node (ref "Q7") (pin "S") (pinfunction "S_S") (pintype "passive"))
      (node (ref "Q8") (pin "S") (pinfunction "S_S") (pintype "passive"))
      (node (ref "R27") (pin "2") (pinfunction "2_2") (pintype "passive"))
      (node (ref "R28") (pin "1") (pinfunction "1_1") (pintype "passive"))
      (node (ref "U4") (pin "44") (pinfunction "SL_A_44") (pintype "passive"))
    )
    (net (code "64") (name "unconnected-(U4-EN_BUCK-Pad55)") (class "Default")
      (node (ref "U4") (pin "55") (pinfunction "EN_BUCK_55") (pintype "passive"))
    )
    (net (code "65") (name "unconnected-(U4-PWRGD-Pad4)") (class "Default")
      (node (ref "U4") (pin "4") (pinfunction "PWRGD_4") (pintype "passive"))
    )
    (net (code "66") (name "unconnected-(U4-SS_TR-Pad56)") (class "Default")
      (node (ref "U4") (pin "56") (pinfunction "SS_TR_56") (pintype "passive"))
    )
  )
)
